# 7-Level_Converter.net
KiCad netlist of a schematic drawn in Altium Designer
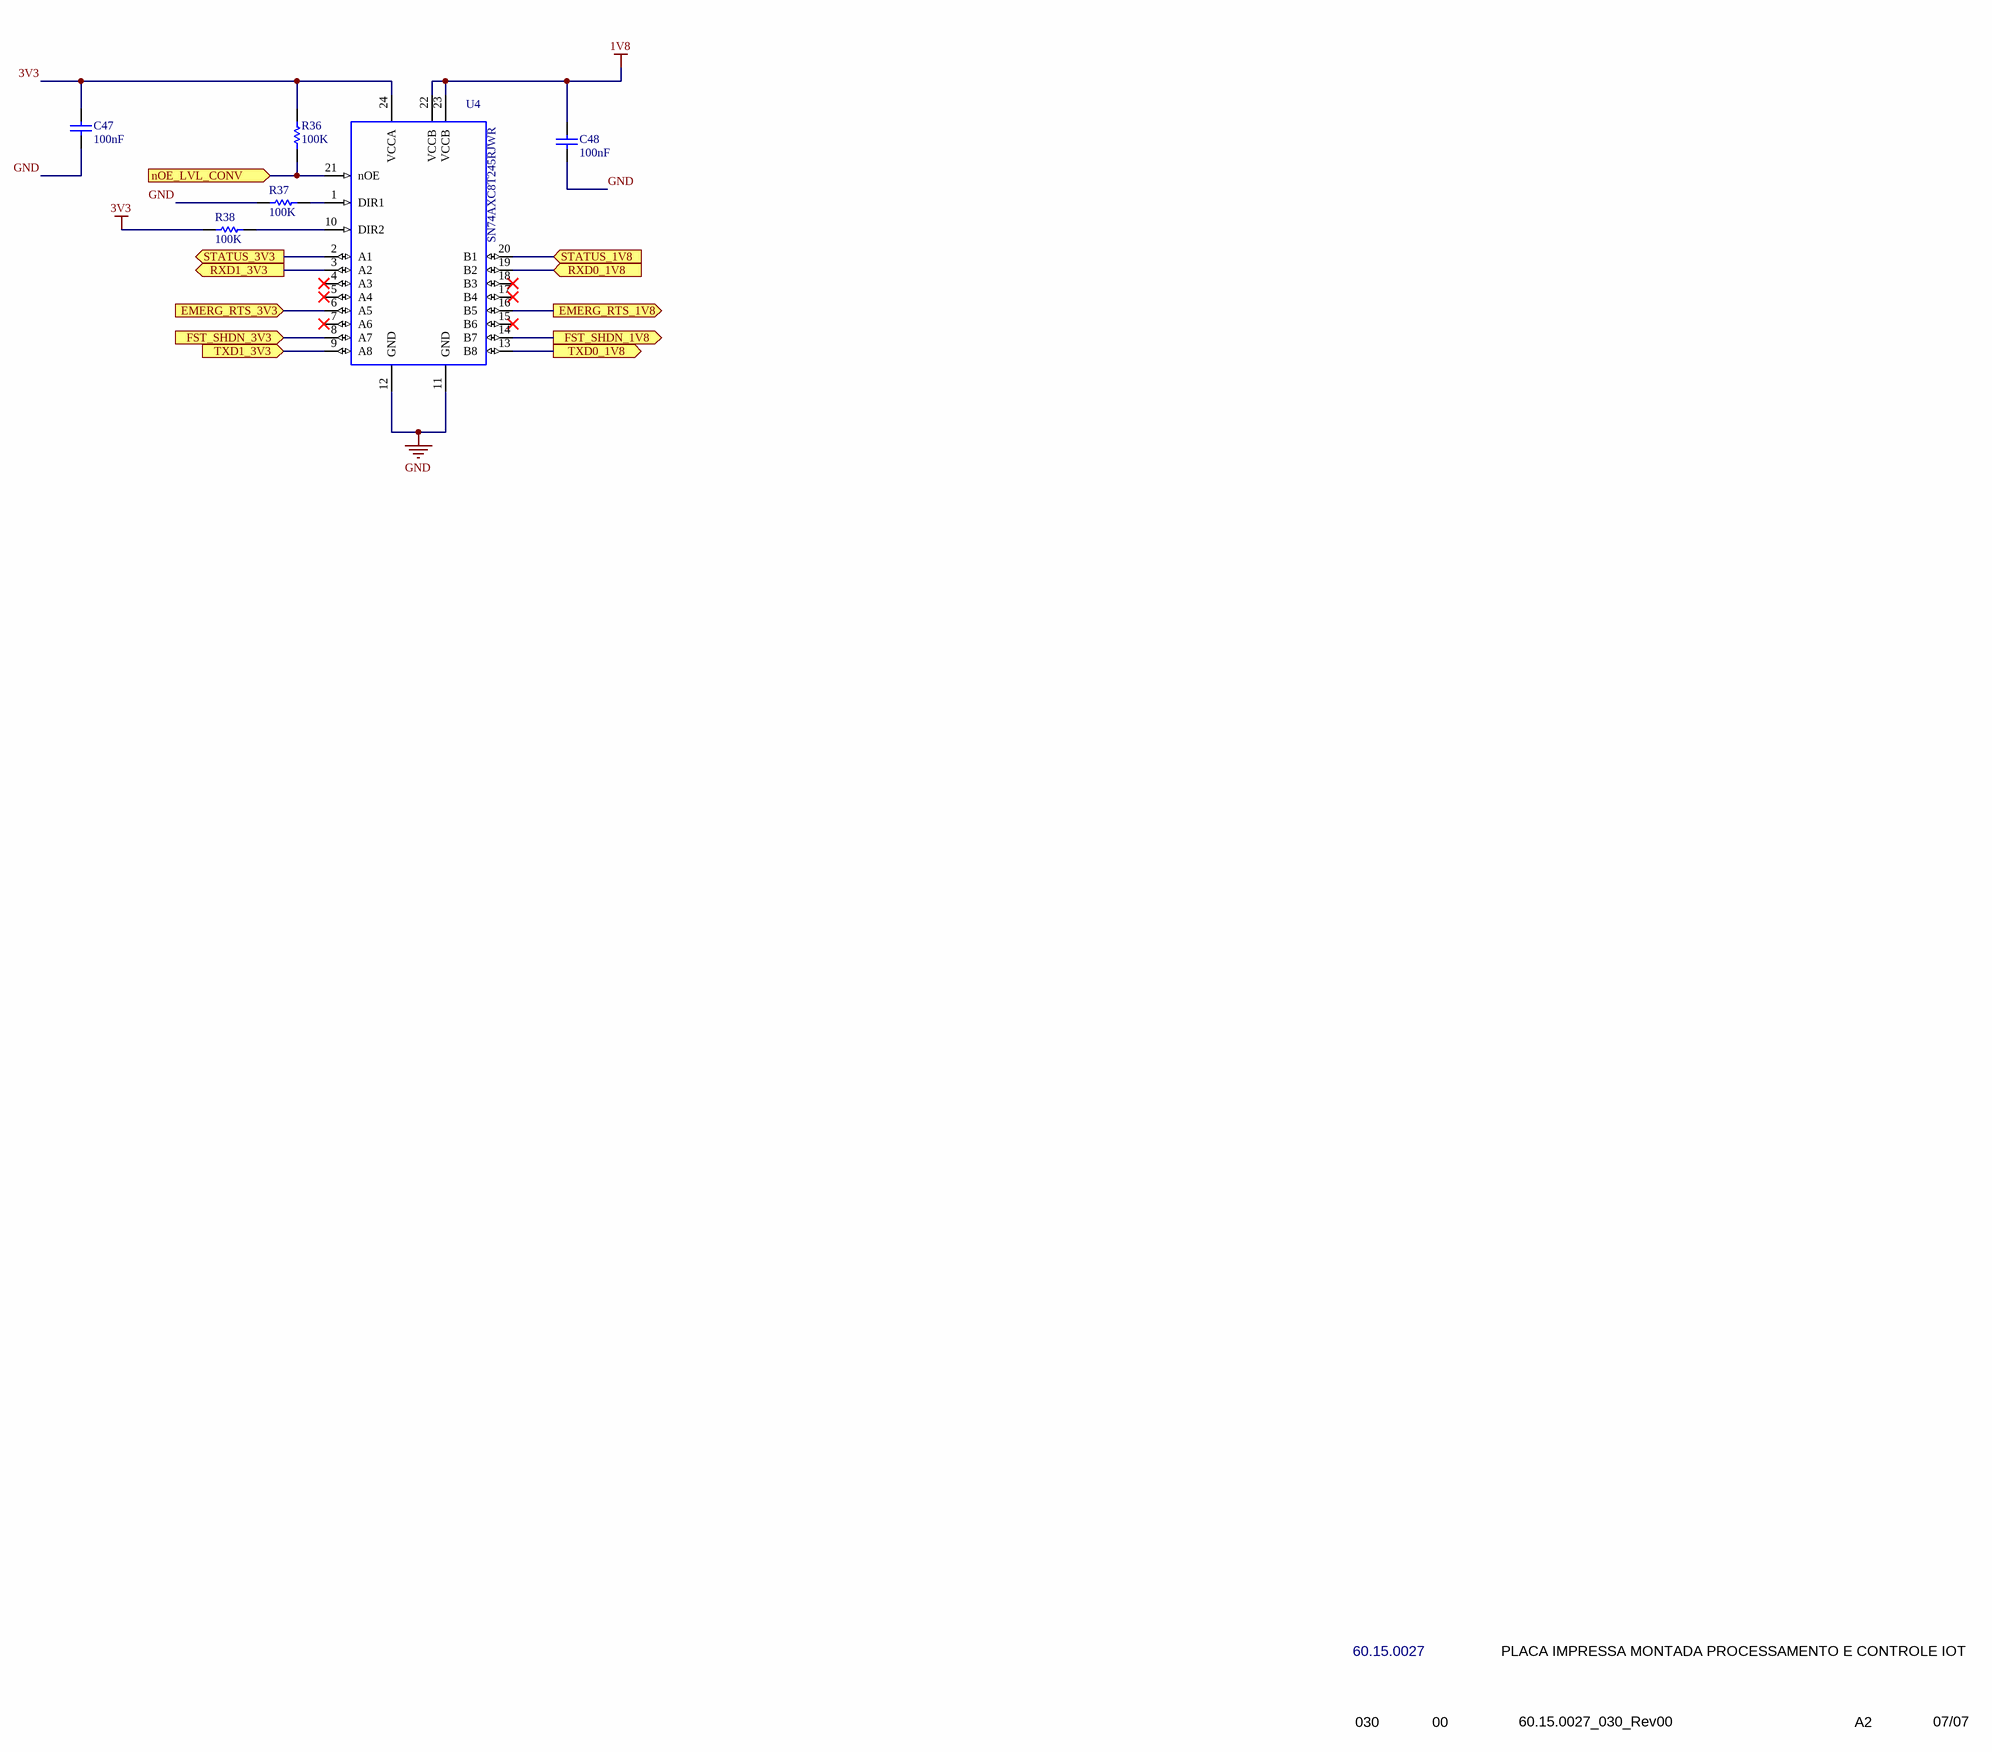
[diagram p0: 7-Level Converter.SchDoc]

(export (version "E")
  (design (tool "Eeschema 10.0.6"))
  (components
    (comp (ref "C47")
      (value "16.23.0803")
      (footprint "16.23.0803")
      (description "CAPACITOR CERAMICO 100nF 16V 10%% X5R SMD 0201")
      (fields (field (name "ALTIUM_UNNAMED_1") "100nF"))
      (libsource (lib "OMNI-CAPACITORES") (part "16.23.0803"))
    )
    (comp (ref "C48")
      (value "16.23.0803")
      (footprint "16.23.0803")
      (description "CAPACITOR CERAMICO 100nF 16V 10%% X5R SMD 0201")
      (fields (field (name "ALTIUM_UNNAMED_1") "100nF"))
      (libsource (lib "OMNI-CAPACITORES") (part "16.23.0803"))
    )
    (comp (ref "R36")
      (value "100K")
      (footprint "66.24.1346")
      (description "RESISTOR THICK FILM 50mW 100K OHMS 1% SMD 0201")
      (fields (field (name "Comment") "66.24.1346"))
      (libsource (lib "OMNI-RESISTORES") (part "66.24.1346"))
    )
    (comp (ref "R37")
      (value "100K")
      (footprint "66.24.1346")
      (description "RESISTOR THICK FILM 50mW 100K OHMS 1% SMD 0201")
      (fields (field (name "Comment") "66.24.1346"))
      (libsource (lib "OMNI-RESISTORES") (part "66.24.1346"))
    )
    (comp (ref "R38")
      (value "100K")
      (footprint "66.24.1346")
      (description "RESISTOR THICK FILM 50mW 100K OHMS 1% SMD 0201")
      (fields (field (name "Comment") "66.24.1346"))
      (libsource (lib "OMNI-RESISTORES") (part "66.24.1346"))
    )
    (comp (ref "U4")
      (value "SN74AXC8T245RJWR")
      (footprint "24.15.0640")
      (description "CID CONVERSOR NIVEL ALIMENTACAO DUPLA DIRECAO CONTROLADA 8 BITS 0.65V - 3.6V")
      (fields (field (name "Comment") "24.15.0640"))
      (libsource (lib "OMNI-CI´S DIGITAIS") (part "24.15.0640"))
    )
  )
  (nets
    (net (code "1") (name "/EMERG_RTS_1V8") (class "Default")
      (node (ref "U4") (pin "16") (pinfunction "B5_16") (pintype "bidirectional"))
    )
    (net (code "2") (name "/EMERG_RTS_3V3") (class "Default")
      (node (ref "U4") (pin "6") (pinfunction "A5_6") (pintype "bidirectional"))
    )
    (net (code "3") (name "/FST_SHDN_1V8") (class "Default")
      (node (ref "U4") (pin "14") (pinfunction "B7_14") (pintype "bidirectional"))
    )
    (net (code "4") (name "/FST_SHDN_3V3") (class "Default")
      (node (ref "U4") (pin "8") (pinfunction "A7_8") (pintype "bidirectional"))
    )
    (net (code "5") (name "/RXD0_1V8") (class "Default")
      (node (ref "U4") (pin "19") (pinfunction "B2_19") (pintype "bidirectional"))
    )
    (net (code "6") (name "/RXD1_3V3") (class "Default")
      (node (ref "U4") (pin "3") (pinfunction "A2_3") (pintype "bidirectional"))
    )
    (net (code "7") (name "/STATUS_1V8") (class "Default")
      (node (ref "U4") (pin "20") (pinfunction "B1_20") (pintype "bidirectional"))
    )
    (net (code "8") (name "/STATUS_3V3") (class "Default")
      (node (ref "U4") (pin "2") (pinfunction "A1_2") (pintype "bidirectional"))
    )
    (net (code "9") (name "/TXD0_1V8") (class "Default")
      (node (ref "U4") (pin "13") (pinfunction "B8_13") (pintype "bidirectional"))
    )
    (net (code "10") (name "/TXD1_3V3") (class "Default")
      (node (ref "U4") (pin "9") (pinfunction "A8_9") (pintype "bidirectional"))
    )
    (net (code "11") (name "/nOE_LVL_CONV") (class "Default")
      (node (ref "R36") (pin "2") (pinfunction "2_2") (pintype "passive"))
      (node (ref "U4") (pin "21") (pinfunction "nOE_21") (pintype "input"))
    )
    (net (code "12") (name "1V8") (class "Default")
      (node (ref "C48") (pin "2") (pinfunction "2_2") (pintype "passive"))
      (node (ref "U4") (pin "22") (pinfunction "VCCB_22") (pintype "power_in"))
      (node (ref "U4") (pin "23") (pinfunction "VCCB_23") (pintype "power_in"))
    )
    (net (code "13") (name "3V3") (class "Default")
      (node (ref "C47") (pin "2") (pinfunction "2_2") (pintype "passive"))
      (node (ref "R36") (pin "1") (pinfunction "1_1") (pintype "passive"))
      (node (ref "R38") (pin "2") (pinfunction "2_2") (pintype "passive"))
      (node (ref "U4") (pin "24") (pinfunction "VCCA_24") (pintype "power_in"))
    )
    (net (code "14") (name "GND") (class "Default")
      (node (ref "C47") (pin "1") (pinfunction "1_1") (pintype "passive"))
      (node (ref "C48") (pin "1") (pinfunction "1_1") (pintype "passive"))
      (node (ref "R37") (pin "2") (pinfunction "2_2") (pintype "passive"))
      (node (ref "U4") (pin "11") (pinfunction "GND_11") (pintype "power_in"))
      (node (ref "U4") (pin "12") (pinfunction "GND_12") (pintype "power_in"))
    )
    (net (code "15") (name "Net-(U4-DIR1)") (class "Default")
      (node (ref "R37") (pin "1") (pinfunction "1_1") (pintype "passive"))
      (node (ref "U4") (pin "1") (pinfunction "DIR1_1") (pintype "input"))
    )
    (net (code "16") (name "Net-(U4-DIR2)") (class "Default")
      (node (ref "R38") (pin "1") (pinfunction "1_1") (pintype "passive"))
      (node (ref "U4") (pin "10") (pinfunction "DIR2_10") (pintype "input"))
    )
    (net (code "17") (name "unconnected-(U4-A3-Pad4)") (class "Default")
      (node (ref "U4") (pin "4") (pinfunction "A3_4") (pintype "bidirectional+no_connect"))
    )
    (net (code "18") (name "unconnected-(U4-A4-Pad5)") (class "Default")
      (node (ref "U4") (pin "5") (pinfunction "A4_5") (pintype "bidirectional+no_connect"))
    )
    (net (code "19") (name "unconnected-(U4-A6-Pad7)") (class "Default")
      (node (ref "U4") (pin "7") (pinfunction "A6_7") (pintype "bidirectional+no_connect"))
    )
    (net (code "20") (name "unconnected-(U4-B3-Pad18)") (class "Default")
      (node (ref "U4") (pin "18") (pinfunction "B3_18") (pintype "bidirectional+no_connect"))
    )
    (net (code "21") (name "unconnected-(U4-B4-Pad17)") (class "Default")
      (node (ref "U4") (pin "17") (pinfunction "B4_17") (pintype "bidirectional+no_connect"))
    )
    (net (code "22") (name "unconnected-(U4-B6-Pad15)") (class "Default")
      (node (ref "U4") (pin "15") (pinfunction "B6_15") (pintype "bidirectional+no_connect"))
    )
  )
)
